# RocketControlver_1_broken.net
KiCad netlist of a schematic drawn in EAGLE
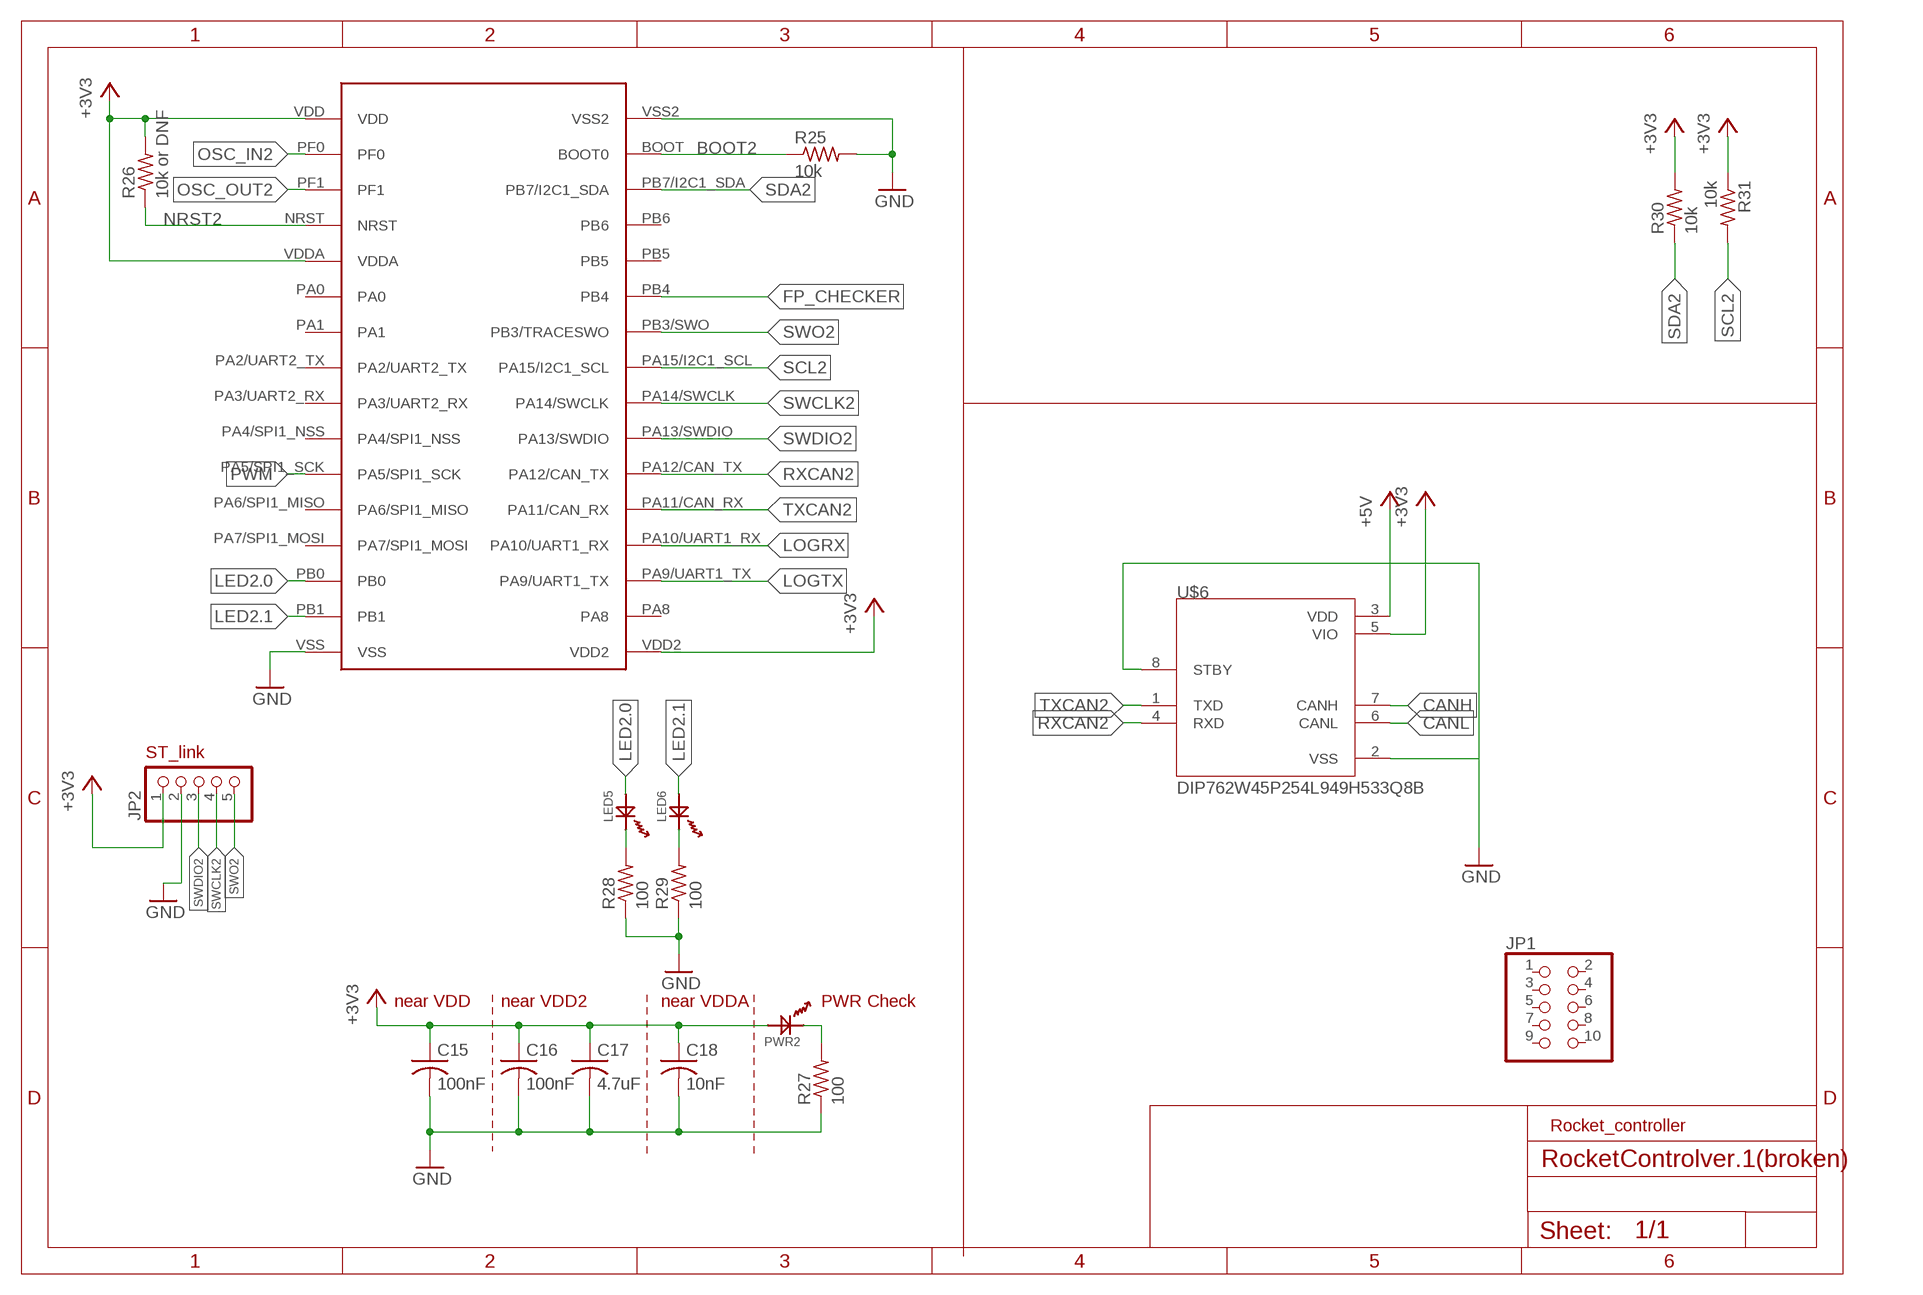
[diagram p0: schematic, sheet 1]

(export (version "E")
  (design (tool "Eeschema 10.0.6"))
  (components
    (comp (ref "C15")
      (value "100nF")
      (footprint "eagle-import:C1608")
      (libsource (lib "eagle-import") (part "C-USC1608"))
    )
    (comp (ref "C16")
      (value "100nF")
      (footprint "eagle-import:C1608")
      (libsource (lib "eagle-import") (part "C-USC1608"))
    )
    (comp (ref "C17")
      (value "4.7uF")
      (footprint "eagle-import:C1608")
      (libsource (lib "eagle-import") (part "C-USC1608"))
    )
    (comp (ref "C18")
      (value "10nF")
      (footprint "eagle-import:C1608")
      (libsource (lib "eagle-import") (part "C-USC1608"))
    )
    (comp (ref "JP1")
      (value "PINHD-2X5/90")
      (footprint "eagle-import:2X05_90")
      (libsource (lib "eagle-import") (part "PINHD-2X5/90"))
    )
    (comp (ref "JP2")
      (value "PINHD-1X5/90")
      (footprint "eagle-import:1X05_90")
      (libsource (lib "eagle-import") (part "PINHD-1X5/90"))
    )
    (comp (ref "LED5")
      (value "OSXX1608C1A")
      (footprint "eagle-import:OSXX1608C1A")
      (libsource (lib "eagle-import") (part "OSXX1608C1A"))
    )
    (comp (ref "LED6")
      (value "OSXX1608C1A")
      (footprint "eagle-import:OSXX1608C1A")
      (libsource (lib "eagle-import") (part "OSXX1608C1A"))
    )
    (comp (ref "PWR2")
      (value "OSXX1608C1A")
      (footprint "eagle-import:OSXX1608C1A")
      (libsource (lib "eagle-import") (part "OSXX1608C1A"))
    )
    (comp (ref "R25")
      (value "10k")
      (footprint "eagle-import:R0603")
      (libsource (lib "eagle-import") (part "R-US_R0603"))
    )
    (comp (ref "R26")
      (value "10k or DNF")
      (footprint "eagle-import:R0603")
      (libsource (lib "eagle-import") (part "R-US_R0603"))
    )
    (comp (ref "R27")
      (value "100")
      (footprint "eagle-import:R0603")
      (libsource (lib "eagle-import") (part "R-US_R0603"))
    )
    (comp (ref "R28")
      (value "100")
      (footprint "eagle-import:R0603")
      (libsource (lib "eagle-import") (part "R-US_R0603"))
    )
    (comp (ref "R29")
      (value "100")
      (footprint "eagle-import:R0603")
      (libsource (lib "eagle-import") (part "R-US_R0603"))
    )
    (comp (ref "R30")
      (value "10k")
      (footprint "eagle-import:R0603")
      (libsource (lib "eagle-import") (part "R-US_R0603"))
    )
    (comp (ref "R31")
      (value "10k")
      (footprint "eagle-import:R0603")
      (libsource (lib "eagle-import") (part "R-US_R0603"))
    )
    (comp (ref "U$1")
      (value "STM32F303K8")
      (footprint "eagle-import:STM32F303K8")
      (libsource (lib "eagle-import") (part "STM32F303K8"))
    )
    (comp (ref "U$6")
      (value "DIP762W45P254L949H533Q8B")
      (footprint "eagle-import:DIP762W45P254L949H533Q8B")
      (libsource (lib "eagle-import") (part "DIP762W45P254L949H533Q8B"))
    )
  )
  (nets
    (net (code "1") (name "+3V3") (class "Default")
      (node (ref "C15") (pin "1") (pinfunction "1_1") (pintype "passive"))
      (node (ref "C16") (pin "1") (pinfunction "1_1") (pintype "passive"))
      (node (ref "C17") (pin "1") (pinfunction "1_1") (pintype "passive"))
      (node (ref "C18") (pin "1") (pinfunction "1_1") (pintype "passive"))
      (node (ref "JP2") (pin "1") (pinfunction "1_1") (pintype "passive"))
      (node (ref "PWR2") (pin "AN") (pinfunction "AN_AN") (pintype "bidirectional"))
      (node (ref "R26") (pin "2") (pinfunction "2_2") (pintype "passive"))
      (node (ref "R30") (pin "2") (pinfunction "2_2") (pintype "passive"))
      (node (ref "R31") (pin "1") (pinfunction "1_1") (pintype "passive"))
      (node (ref "U$1") (pin "VDD") (pinfunction "VDD_VDD") (pintype "power_in"))
      (node (ref "U$1") (pin "VDD2") (pinfunction "VDD2_VDD2") (pintype "power_in"))
      (node (ref "U$1") (pin "VDDA") (pinfunction "VDDA_VDDA") (pintype "power_in"))
      (node (ref "U$6") (pin "5") (pinfunction "VIO_5") (pintype "power_in"))
    )
    (net (code "2") (name "+5V") (class "Default")
      (node (ref "U$6") (pin "3") (pinfunction "VDD_3") (pintype "power_in"))
    )
    (net (code "3") (name "/BOOT2") (class "Default")
      (node (ref "R25") (pin "1") (pinfunction "1_1") (pintype "passive"))
      (node (ref "U$1") (pin "BOOT") (pinfunction "BOOT0_BOOT") (pintype "bidirectional"))
    )
    (net (code "4") (name "/NRST2") (class "Default")
      (node (ref "R26") (pin "1") (pinfunction "1_1") (pintype "passive"))
      (node (ref "U$1") (pin "NRST") (pinfunction "NRST_NRST") (pintype "bidirectional"))
    )
    (net (code "5") (name "CANH") (class "Default")
      (node (ref "U$6") (pin "7") (pinfunction "CANH_7") (pintype "bidirectional"))
    )
    (net (code "6") (name "CANL") (class "Default")
      (node (ref "U$6") (pin "6") (pinfunction "CANL_6") (pintype "bidirectional"))
    )
    (net (code "7") (name "FP_CHECKER") (class "Default")
      (node (ref "U$1") (pin "PB4") (pinfunction "PB4_PB4") (pintype "bidirectional"))
    )
    (net (code "8") (name "GND") (class "Default")
      (node (ref "C15") (pin "2") (pinfunction "2_2") (pintype "passive"))
      (node (ref "C16") (pin "2") (pinfunction "2_2") (pintype "passive"))
      (node (ref "C17") (pin "2") (pinfunction "2_2") (pintype "passive"))
      (node (ref "C18") (pin "2") (pinfunction "2_2") (pintype "passive"))
      (node (ref "JP2") (pin "2") (pinfunction "2_2") (pintype "passive"))
      (node (ref "R25") (pin "2") (pinfunction "2_2") (pintype "passive"))
      (node (ref "R27") (pin "1") (pinfunction "1_1") (pintype "passive"))
      (node (ref "R28") (pin "1") (pinfunction "1_1") (pintype "passive"))
      (node (ref "R29") (pin "1") (pinfunction "1_1") (pintype "passive"))
      (node (ref "U$1") (pin "VSS") (pinfunction "VSS_VSS") (pintype "power_in"))
      (node (ref "U$1") (pin "VSS2") (pinfunction "VSS2_VSS2") (pintype "power_in"))
      (node (ref "U$6") (pin "2") (pinfunction "VSS_2") (pintype "power_in"))
      (node (ref "U$6") (pin "8") (pinfunction "STBY_8") (pintype "input"))
    )
    (net (code "9") (name "LED2.0") (class "Default")
      (node (ref "LED5") (pin "AN") (pinfunction "AN_AN") (pintype "bidirectional"))
      (node (ref "U$1") (pin "PB0") (pinfunction "PB0_PB0") (pintype "bidirectional"))
    )
    (net (code "10") (name "LED2.1") (class "Default")
      (node (ref "LED6") (pin "AN") (pinfunction "AN_AN") (pintype "bidirectional"))
      (node (ref "U$1") (pin "PB1") (pinfunction "PB1_PB1") (pintype "bidirectional"))
    )
    (net (code "11") (name "LOGRX") (class "Default")
      (node (ref "U$1") (pin "PA10/UART1_RX") (pinfunction "PA10/UART1_RX_PA10/UART1_RX") (pintype "bidirectional"))
    )
    (net (code "12") (name "LOGTX") (class "Default")
      (node (ref "U$1") (pin "PA9/UART1_TX") (pinfunction "PA9/UART1_TX_PA9/UART1_TX") (pintype "bidirectional"))
    )
    (net (code "13") (name "Net-(LED5-PadCT)") (class "Default")
      (node (ref "LED5") (pin "CT") (pinfunction "CT_CT") (pintype "bidirectional"))
      (node (ref "R28") (pin "2") (pinfunction "2_2") (pintype "passive"))
    )
    (net (code "14") (name "Net-(LED6-PadCT)") (class "Default")
      (node (ref "LED6") (pin "CT") (pinfunction "CT_CT") (pintype "bidirectional"))
      (node (ref "R29") (pin "2") (pinfunction "2_2") (pintype "passive"))
    )
    (net (code "15") (name "Net-(PWR2-PadCT)") (class "Default")
      (node (ref "PWR2") (pin "CT") (pinfunction "CT_CT") (pintype "bidirectional"))
      (node (ref "R27") (pin "2") (pinfunction "2_2") (pintype "passive"))
    )
    (net (code "16") (name "OSC_IN2") (class "Default")
      (node (ref "U$1") (pin "PF0") (pinfunction "PF0_PF0") (pintype "bidirectional"))
    )
    (net (code "17") (name "OSC_OUT2") (class "Default")
      (node (ref "U$1") (pin "PF1") (pinfunction "PF1_PF1") (pintype "bidirectional"))
    )
    (net (code "18") (name "PWM") (class "Default")
      (node (ref "U$1") (pin "PA5/SPI1_SCK") (pinfunction "PA5/SPI1_SCK_PA5/SPI1_SCK") (pintype "bidirectional"))
    )
    (net (code "19") (name "RXCAN2") (class "Default")
      (node (ref "U$1") (pin "PA12/CAN_TX") (pinfunction "PA12/CAN_TX_PA12/CAN_TX") (pintype "bidirectional"))
      (node (ref "U$6") (pin "4") (pinfunction "RXD_4") (pintype "output"))
    )
    (net (code "20") (name "SCL2") (class "Default")
      (node (ref "R31") (pin "2") (pinfunction "2_2") (pintype "passive"))
      (node (ref "U$1") (pin "PA15/I2C1_SCL") (pinfunction "PA15/I2C1_SCL_PA15/I2C1_SCL") (pintype "bidirectional"))
    )
    (net (code "21") (name "SDA2") (class "Default")
      (node (ref "R30") (pin "1") (pinfunction "1_1") (pintype "passive"))
      (node (ref "U$1") (pin "PB7/I2C1_SDA") (pinfunction "PB7/I2C1_SDA_PB7/I2C1_SDA") (pintype "bidirectional"))
    )
    (net (code "22") (name "SWCLK2") (class "Default")
      (node (ref "JP2") (pin "4") (pinfunction "4_4") (pintype "passive"))
      (node (ref "U$1") (pin "PA14/SWCLK") (pinfunction "PA14/SWCLK_PA14/SWCLK") (pintype "bidirectional"))
    )
    (net (code "23") (name "SWDIO2") (class "Default")
      (node (ref "JP2") (pin "3") (pinfunction "3_3") (pintype "passive"))
      (node (ref "U$1") (pin "PA13/SWDIO") (pinfunction "PA13/SWDIO_PA13/SWDIO") (pintype "bidirectional"))
    )
    (net (code "24") (name "SWO2") (class "Default")
      (node (ref "JP2") (pin "5") (pinfunction "5_5") (pintype "passive"))
      (node (ref "U$1") (pin "PB3/SWO") (pinfunction "PB3/TRACESWO_PB3/SWO") (pintype "bidirectional"))
    )
    (net (code "25") (name "TXCAN2") (class "Default")
      (node (ref "U$1") (pin "PA11/CAN_RX") (pinfunction "PA11/CAN_RX_PA11/CAN_RX") (pintype "bidirectional"))
      (node (ref "U$6") (pin "1") (pinfunction "TXD_1") (pintype "input"))
    )
    (net (code "26") (name "unconnected-(JP1-Pad1)") (class "Default")
      (node (ref "JP1") (pin "1") (pinfunction "1_1") (pintype "passive"))
    )
    (net (code "27") (name "unconnected-(JP1-Pad2)") (class "Default")
      (node (ref "JP1") (pin "2") (pinfunction "2_2") (pintype "passive"))
    )
    (net (code "28") (name "unconnected-(JP1-Pad3)") (class "Default")
      (node (ref "JP1") (pin "3") (pinfunction "3_3") (pintype "passive"))
    )
    (net (code "29") (name "unconnected-(JP1-Pad4)") (class "Default")
      (node (ref "JP1") (pin "4") (pinfunction "4_4") (pintype "passive"))
    )
    (net (code "30") (name "unconnected-(JP1-Pad5)") (class "Default")
      (node (ref "JP1") (pin "5") (pinfunction "5_5") (pintype "passive"))
    )
    (net (code "31") (name "unconnected-(JP1-Pad6)") (class "Default")
      (node (ref "JP1") (pin "6") (pinfunction "6_6") (pintype "passive"))
    )
    (net (code "32") (name "unconnected-(JP1-Pad7)") (class "Default")
      (node (ref "JP1") (pin "7") (pinfunction "7_7") (pintype "passive"))
    )
    (net (code "33") (name "unconnected-(JP1-Pad8)") (class "Default")
      (node (ref "JP1") (pin "8") (pinfunction "8_8") (pintype "passive"))
    )
    (net (code "34") (name "unconnected-(JP1-Pad9)") (class "Default")
      (node (ref "JP1") (pin "9") (pinfunction "9_9") (pintype "passive"))
    )
    (net (code "35") (name "unconnected-(JP1-Pad10)") (class "Default")
      (node (ref "JP1") (pin "10") (pinfunction "10_10") (pintype "passive"))
    )
    (net (code "36") (name "unconnected-(U$1-PadPA0)") (class "Default")
      (node (ref "U$1") (pin "PA0") (pinfunction "PA0_PA0") (pintype "bidirectional"))
    )
    (net (code "37") (name "unconnected-(U$1-PadPA1)") (class "Default")
      (node (ref "U$1") (pin "PA1") (pinfunction "PA1_PA1") (pintype "bidirectional"))
    )
    (net (code "38") (name "unconnected-(U$1-PadPA2{slash}UART2_TX)") (class "Default")
      (node (ref "U$1") (pin "PA2/UART2_TX") (pinfunction "PA2/UART2_TX_PA2/UART2_TX") (pintype "bidirectional"))
    )
    (net (code "39") (name "unconnected-(U$1-PadPA3{slash}UART2_RX)") (class "Default")
      (node (ref "U$1") (pin "PA3/UART2_RX") (pinfunction "PA3/UART2_RX_PA3/UART2_RX") (pintype "bidirectional"))
    )
    (net (code "40") (name "unconnected-(U$1-PadPA4{slash}SPI1_NSS)") (class "Default")
      (node (ref "U$1") (pin "PA4/SPI1_NSS") (pinfunction "PA4/SPI1_NSS_PA4/SPI1_NSS") (pintype "bidirectional"))
    )
    (net (code "41") (name "unconnected-(U$1-PadPA6{slash}SPI1_MISO)") (class "Default")
      (node (ref "U$1") (pin "PA6/SPI1_MISO") (pinfunction "PA6/SPI1_MISO_PA6/SPI1_MISO") (pintype "bidirectional"))
    )
    (net (code "42") (name "unconnected-(U$1-PadPA7{slash}SPI1_MOSI)") (class "Default")
      (node (ref "U$1") (pin "PA7/SPI1_MOSI") (pinfunction "PA7/SPI1_MOSI_PA7/SPI1_MOSI") (pintype "bidirectional"))
    )
    (net (code "43") (name "unconnected-(U$1-PadPA8)") (class "Default")
      (node (ref "U$1") (pin "PA8") (pinfunction "PA8_PA8") (pintype "bidirectional"))
    )
    (net (code "44") (name "unconnected-(U$1-PadPB5)") (class "Default")
      (node (ref "U$1") (pin "PB5") (pinfunction "PB5_PB5") (pintype "bidirectional"))
    )
    (net (code "45") (name "unconnected-(U$1-PadPB6)") (class "Default")
      (node (ref "U$1") (pin "PB6") (pinfunction "PB6_PB6") (pintype "bidirectional"))
    )
  )
)
